# Infinity_Mirror.net
KiCad netlist of a schematic drawn in EAGLE
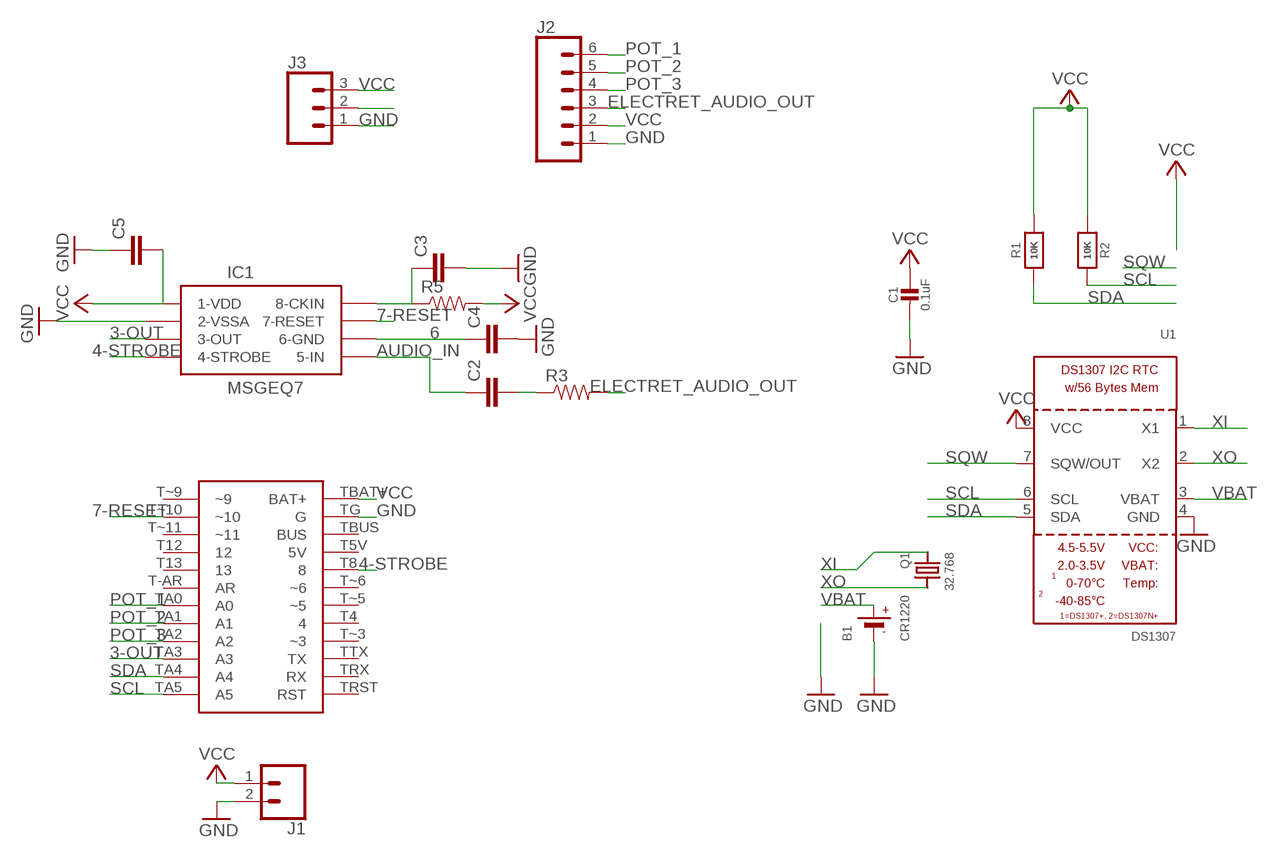
[diagram p0: schematic, sheet 1]

(export (version "E")
  (design (tool "Eeschema 10.0.6"))
  (components
    (comp (ref "B1")
      (value "CR1220")
      (footprint "eagle-import:CR1220")
      (libsource (lib "eagle-import") (part "BATTERYCR1220_SMT"))
    )
    (comp (ref "C1")
      (value "0.1uF")
      (footprint "eagle-import:0805-NO")
      (libsource (lib "eagle-import") (part "CAP_CERAMIC0805-NOOUTLINE"))
    )
    (comp (ref "C2")
      (value "SPARKFUN-CAPACITORS_CAP0805")
      (footprint "eagle-import:SPARKFUN-CAPACITORS_0805")
      (libsource (lib "eagle-import") (part "SPARKFUN-CAPACITORS_CAP0805"))
    )
    (comp (ref "C3")
      (value "SPARKFUN-CAPACITORS_CAP0805")
      (footprint "eagle-import:SPARKFUN-CAPACITORS_0805")
      (libsource (lib "eagle-import") (part "SPARKFUN-CAPACITORS_CAP0805"))
    )
    (comp (ref "C4")
      (value "SPARKFUN-CAPACITORS_CAP0805")
      (footprint "eagle-import:SPARKFUN-CAPACITORS_0805")
      (libsource (lib "eagle-import") (part "SPARKFUN-CAPACITORS_CAP0805"))
    )
    (comp (ref "C5")
      (value "SPARKFUN-CAPACITORS_CAP0805")
      (footprint "eagle-import:SPARKFUN-CAPACITORS_0805")
      (libsource (lib "eagle-import") (part "SPARKFUN-CAPACITORS_CAP0805"))
    )
    (comp (ref "IC1")
      (value "MSGEQ7P")
      (footprint "eagle-import:DIP08")
      (libsource (lib "eagle-import") (part "MSGEQ7DIL"))
    )
    (comp (ref "J1")
      (value "SPARKFUN-CONNECTORS_CONN_02LOCK")
      (footprint "eagle-import:SPARKFUN-CONNECTORS_1X02_LOCK")
      (libsource (lib "eagle-import") (part "SPARKFUN-CONNECTORS_CONN_02LOCK"))
    )
    (comp (ref "J2")
      (value "CONN_06SILK_FEMALE_PTH")
      (footprint "eagle-import:1X06")
      (libsource (lib "eagle-import") (part "CONN_06SILK_FEMALE_PTH"))
    )
    (comp (ref "J3")
      (value "CONN_03")
      (footprint "eagle-import:1X03")
      (libsource (lib "eagle-import") (part "CONN_03"))
    )
    (comp (ref "Q1")
      (value "32.768")
      (footprint "eagle-import:CRYSTAL_8X3.8")
      (libsource (lib "eagle-import") (part "CRYSTAL8.0X3.8"))
    )
    (comp (ref "R1")
      (value "10K")
      (footprint "eagle-import:0805-NO")
      (libsource (lib "eagle-import") (part "RESISTOR0805_NOOUTLINE"))
    )
    (comp (ref "R2")
      (value "10K")
      (footprint "eagle-import:0805-NO")
      (libsource (lib "eagle-import") (part "RESISTOR0805_NOOUTLINE"))
    )
    (comp (ref "R3")
      (value "SPARKFUN-PASSIVES_RESISTOR0805-RES")
      (footprint "eagle-import:SPARKFUN-PASSIVES_0805")
      (libsource (lib "eagle-import") (part "SPARKFUN-PASSIVES_RESISTOR0805-RES"))
    )
    (comp (ref "R5")
      (value "SPARKFUN-PASSIVES_RESISTOR0805-RES")
      (footprint "eagle-import:SPARKFUN-PASSIVES_0805")
      (libsource (lib "eagle-import") (part "SPARKFUN-PASSIVES_RESISTOR0805-RES"))
    )
    (comp (ref "U$1")
      (value "ADAFRUIT_PRO_TRINKET_NO-DIMENSION")
      (footprint "eagle-import:ARDUINO_PRO_TRINKET_5V_NO-DIMENSION")
      (libsource (lib "eagle-import") (part "ADAFRUIT_PRO_TRINKET_NO-DIMENSION"))
    )
    (comp (ref "U1")
      (value "DS1307")
      (footprint "eagle-import:SOIC8_150MIL")
      (libsource (lib "eagle-import") (part "RTC_DS1307"))
    )
  )
  (nets
    (net (code "1") (name "/3-OUT") (class "Default")
      (node (ref "IC1") (pin "3") (pinfunction "3-OUT_3") (pintype "input"))
      (node (ref "U$1") (pin "TA3") (pinfunction "A3_TA3") (pintype "bidirectional"))
    )
    (net (code "2") (name "/4-STROBE") (class "Default")
      (node (ref "IC1") (pin "4") (pinfunction "4-STROBE_4") (pintype "input"))
      (node (ref "U$1") (pin "T8") (pinfunction "8_T8") (pintype "bidirectional"))
    )
    (net (code "3") (name "/6") (class "Default")
      (node (ref "C4") (pin "1") (pinfunction "1_1") (pintype "passive"))
      (node (ref "IC1") (pin "6") (pinfunction "6-GND_6") (pintype "bidirectional"))
    )
    (net (code "4") (name "/7-RESET") (class "Default")
      (node (ref "IC1") (pin "7") (pinfunction "7-RESET_7") (pintype "bidirectional"))
      (node (ref "U$1") (pin "T~10") (pinfunction "~{10}_T~10") (pintype "bidirectional"))
    )
    (net (code "5") (name "/AUDIO_IN") (class "Default")
      (node (ref "C2") (pin "1") (pinfunction "1_1") (pintype "passive"))
      (node (ref "IC1") (pin "5") (pinfunction "5-IN_5") (pintype "bidirectional"))
    )
    (net (code "6") (name "/ELECTRET_AUDIO_OUT") (class "Default")
      (node (ref "J2") (pin "3") (pinfunction "3_3") (pintype "passive"))
      (node (ref "R3") (pin "2") (pinfunction "2_2") (pintype "passive"))
    )
    (net (code "7") (name "/POT_1") (class "Default")
      (node (ref "J2") (pin "6") (pinfunction "6_6") (pintype "passive"))
      (node (ref "U$1") (pin "TA0") (pinfunction "A0_TA0") (pintype "bidirectional"))
    )
    (net (code "8") (name "/POT_2") (class "Default")
      (node (ref "J2") (pin "5") (pinfunction "5_5") (pintype "passive"))
      (node (ref "U$1") (pin "TA1") (pinfunction "A1_TA1") (pintype "bidirectional"))
    )
    (net (code "9") (name "/POT_3") (class "Default")
      (node (ref "J2") (pin "4") (pinfunction "4_4") (pintype "passive"))
      (node (ref "U$1") (pin "TA2") (pinfunction "A2_TA2") (pintype "bidirectional"))
    )
    (net (code "10") (name "/SCL") (class "Default")
      (node (ref "R2") (pin "2") (pinfunction "2_2") (pintype "passive"))
      (node (ref "U$1") (pin "TA5") (pinfunction "A5_TA5") (pintype "bidirectional"))
      (node (ref "U1") (pin "6") (pinfunction "SCL_6") (pintype "bidirectional"))
    )
    (net (code "11") (name "/SDA") (class "Default")
      (node (ref "R1") (pin "1") (pinfunction "1_1") (pintype "passive"))
      (node (ref "U$1") (pin "TA4") (pinfunction "A4_TA4") (pintype "bidirectional"))
      (node (ref "U1") (pin "5") (pinfunction "SDA_5") (pintype "bidirectional"))
    )
    (net (code "12") (name "/SQW") (class "Default")
      (node (ref "U1") (pin "7") (pinfunction "SQW/OUT_7") (pintype "bidirectional"))
    )
    (net (code "13") (name "/VBAT") (class "Default")
      (node (ref "B1") (pin "+$1") (pinfunction "+_+$1") (pintype "passive"))
      (node (ref "U1") (pin "3") (pinfunction "VBAT_3") (pintype "bidirectional"))
    )
    (net (code "14") (name "/XI") (class "Default")
      (node (ref "Q1") (pin "P$1") (pinfunction "1_P$1") (pintype "passive"))
      (node (ref "U1") (pin "1") (pinfunction "X1_1") (pintype "bidirectional"))
    )
    (net (code "15") (name "/XO") (class "Default")
      (node (ref "Q1") (pin "P$4") (pinfunction "2_P$4") (pintype "passive"))
      (node (ref "U1") (pin "2") (pinfunction "X2_2") (pintype "bidirectional"))
    )
    (net (code "16") (name "GND") (class "Default")
      (node (ref "B1") (pin "-") (pinfunction "-_-") (pintype "passive"))
      (node (ref "C1") (pin "2") (pinfunction "2_2") (pintype "passive"))
      (node (ref "C3") (pin "2") (pinfunction "2_2") (pintype "passive"))
      (node (ref "C4") (pin "2") (pinfunction "2_2") (pintype "passive"))
      (node (ref "C5") (pin "1") (pinfunction "1_1") (pintype "passive"))
      (node (ref "IC1") (pin "2") (pinfunction "2-VSSA_2") (pintype "input"))
      (node (ref "J1") (pin "2") (pinfunction "2_2") (pintype "passive"))
      (node (ref "J2") (pin "1") (pinfunction "1_1") (pintype "passive"))
      (node (ref "J3") (pin "1") (pinfunction "1_1") (pintype "passive"))
      (node (ref "U$1") (pin "TG") (pinfunction "G_TG") (pintype "bidirectional"))
      (node (ref "U1") (pin "4") (pinfunction "GND_4") (pintype "bidirectional"))
    )
    (net (code "17") (name "Net-(C2-Pad2)") (class "Default")
      (node (ref "C2") (pin "2") (pinfunction "2_2") (pintype "passive"))
      (node (ref "R3") (pin "1") (pinfunction "1_1") (pintype "passive"))
    )
    (net (code "18") (name "Net-(IC1-8-CKIN)") (class "Default")
      (node (ref "C3") (pin "1") (pinfunction "1_1") (pintype "passive"))
      (node (ref "IC1") (pin "8") (pinfunction "8-CKIN_8") (pintype "bidirectional"))
      (node (ref "R5") (pin "1") (pinfunction "1_1") (pintype "passive"))
    )
    (net (code "19") (name "VCC") (class "Default")
      (node (ref "C1") (pin "1") (pinfunction "1_1") (pintype "passive"))
      (node (ref "C5") (pin "2") (pinfunction "2_2") (pintype "passive"))
      (node (ref "IC1") (pin "1") (pinfunction "1-VDD_1") (pintype "input"))
      (node (ref "J1") (pin "1") (pinfunction "1_1") (pintype "passive"))
      (node (ref "J2") (pin "2") (pinfunction "2_2") (pintype "passive"))
      (node (ref "J3") (pin "3") (pinfunction "3_3") (pintype "passive"))
      (node (ref "R1") (pin "2") (pinfunction "2_2") (pintype "passive"))
      (node (ref "R2") (pin "1") (pinfunction "1_1") (pintype "passive"))
      (node (ref "R5") (pin "2") (pinfunction "2_2") (pintype "passive"))
      (node (ref "U$1") (pin "TBAT+") (pinfunction "BAT+_TBAT+") (pintype "bidirectional"))
      (node (ref "U1") (pin "8") (pinfunction "VCC_8") (pintype "bidirectional"))
    )
    (net (code "20") (name "unconnected-(J3-Pad2)") (class "Default")
      (node (ref "J3") (pin "2") (pinfunction "2_2") (pintype "passive"))
    )
    (net (code "21") (name "unconnected-(U$1-4-PadT4)") (class "Default")
      (node (ref "U$1") (pin "T4") (pinfunction "4_T4") (pintype "bidirectional"))
    )
    (net (code "22") (name "unconnected-(U$1-5V-PadT5V)") (class "Default")
      (node (ref "U$1") (pin "T5V") (pinfunction "5V_T5V") (pintype "bidirectional"))
    )
    (net (code "23") (name "unconnected-(U$1-12-PadT12)") (class "Default")
      (node (ref "U$1") (pin "T12") (pinfunction "12_T12") (pintype "bidirectional"))
    )
    (net (code "24") (name "unconnected-(U$1-13-PadT13)") (class "Default")
      (node (ref "U$1") (pin "T13") (pinfunction "13_T13") (pintype "bidirectional"))
    )
    (net (code "25") (name "unconnected-(U$1-AR-PadT-AR)") (class "Default")
      (node (ref "U$1") (pin "T-AR") (pinfunction "AR_T-AR") (pintype "bidirectional"))
    )
    (net (code "26") (name "unconnected-(U$1-BUS-PadTBUS)") (class "Default")
      (node (ref "U$1") (pin "TBUS") (pinfunction "BUS_TBUS") (pintype "bidirectional"))
    )
    (net (code "27") (name "unconnected-(U$1-RST-PadTRST)") (class "Default")
      (node (ref "U$1") (pin "TRST") (pinfunction "RST_TRST") (pintype "bidirectional"))
    )
    (net (code "28") (name "unconnected-(U$1-RX-PadTRX)") (class "Default")
      (node (ref "U$1") (pin "TRX") (pinfunction "RX_TRX") (pintype "bidirectional"))
    )
    (net (code "29") (name "unconnected-(U$1-TX-PadTTX)") (class "Default")
      (node (ref "U$1") (pin "TTX") (pinfunction "TX_TTX") (pintype "bidirectional"))
    )
    (net (code "30") (name "unconnected-(U$1-~{3}-PadT~3)") (class "Default")
      (node (ref "U$1") (pin "T~3") (pinfunction "~{3}_T~3") (pintype "bidirectional"))
    )
    (net (code "31") (name "unconnected-(U$1-~{5}-PadT~5)") (class "Default")
      (node (ref "U$1") (pin "T~5") (pinfunction "~{5}_T~5") (pintype "bidirectional"))
    )
    (net (code "32") (name "unconnected-(U$1-~{6}-PadT~6)") (class "Default")
      (node (ref "U$1") (pin "T~6") (pinfunction "~{6}_T~6") (pintype "bidirectional"))
    )
    (net (code "33") (name "unconnected-(U$1-~{9}-PadT~9)") (class "Default")
      (node (ref "U$1") (pin "T~9") (pinfunction "~{9}_T~9") (pintype "bidirectional"))
    )
    (net (code "34") (name "unconnected-(U$1-~{11}-PadT~11)") (class "Default")
      (node (ref "U$1") (pin "T~11") (pinfunction "~{11}_T~11") (pintype "bidirectional"))
    )
  )
)
